# Logic_Level_Output.net
KiCad netlist of a schematic drawn in Altium Designer
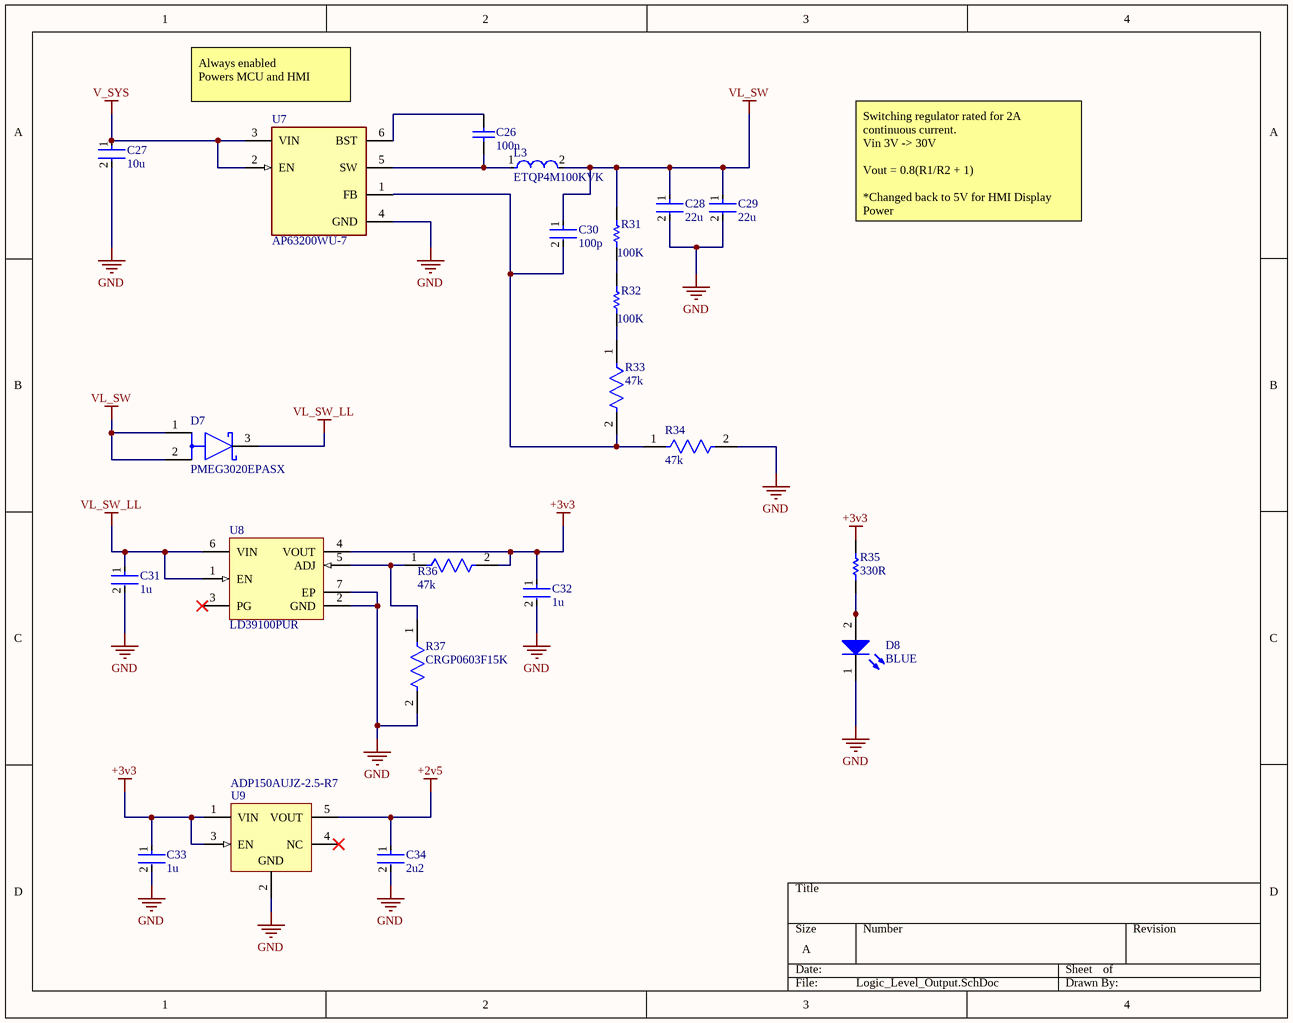
[diagram p0: Logic_Level_Output.SchDoc]

(export (version "E")
  (design (tool "Eeschema 10.0.6"))
  (components
    (comp (ref "C26")
      (value "100n")
      (footprint "CAPC1608X90X35NL15T15")
      (fields (field (name "PART NUMBER") "C0603C104K4RAC7013") (field (name "MANUFACTURER") "Kemet"))
      (libsource (lib "Altium Content Vault") (part "CAP"))
    )
    (comp (ref "C27")
      (value "10u")
      (footprint "FP-C0805X106K8RACAUTO-MFG")
      (description "CAP CER 10UF 10V X7R 0805")
      (fields (field (name "TOLERANCE") "10%"))
      (libsource (lib "Altium Content Vault") (part "b4654b650e69147ec39a6b967a45e02"))
    )
    (comp (ref "C28")
      (value "22u")
      (footprint "FP-C0805C226M8PACTU-MFG")
      (description "CAP CER 22UF 10V X5R 0805")
      (fields (field (name "TOLERANCE") "20%") (field (name "VOLTAGE") "10V"))
      (libsource (lib "Altium Content Vault") (part "02cd4be3c70576c341d710602a673aa"))
    )
    (comp (ref "C29")
      (value "22u")
      (footprint "FP-C0805C226M8PACTU-MFG")
      (description "CAP CER 22UF 10V X5R 0805")
      (fields (field (name "TOLERANCE") "20%") (field (name "VOLTAGE") "10V"))
      (libsource (lib "Altium Content Vault") (part "02cd4be3c70576c341d710602a673aa"))
    )
    (comp (ref "C30")
      (value "100p")
      (footprint "FP-C0603C-CF-MFG")
      (description "CAP CER 100PF 10V X7R 0603")
      (fields
        (field (name "MANUFACTURER") "KEMET")
        (field (name "OCTOPART") "https://octopart.com/c0603c101k8rac7867-kemet-83501928")
      )
      (libsource (lib "Altium Content Vault") (part "b4654b650e69147ec39a6b967a45e02"))
    )
    (comp (ref "C31")
      (value "1u")
      (footprint "FP-0603-L_1_6_0_15-W_0_81-IPC_A")
      (description "General Purpose Ceramic Capacitor, 0603, 1uF, 10%, X5R, 15%, 6.3V")
      (fields (field (name "VOLTAGE") "6.3V") (field (name "TOLERANCE") "10%"))
      (libsource (lib "Altium Content Vault") (part "02cd4be3c70576c341d710602a673aa"))
    )
    (comp (ref "C32")
      (value "1u")
      (footprint "FP-0603-L_1_6_0_15-W_0_81-IPC_A")
      (description "General Purpose Ceramic Capacitor, 0603, 1uF, 10%, X5R, 15%, 6.3V")
      (fields (field (name "VOLTAGE") "6.3V") (field (name "TOLERANCE") "10%"))
      (libsource (lib "Altium Content Vault") (part "02cd4be3c70576c341d710602a673aa"))
    )
    (comp (ref "C33")
      (value "1u")
      (footprint "FP-0603-L_1_6_0_15-W_0_81-IPC_A")
      (description "General Purpose Ceramic Capacitor, 0603, 1uF, 10%, X5R, 15%, 6.3V")
      (fields (field (name "VOLTAGE") "6.3V") (field (name "TOLERANCE") "10%"))
      (libsource (lib "Altium Content Vault") (part "02cd4be3c70576c341d710602a673aa"))
    )
    (comp (ref "C34")
      (value "2u2")
      (footprint "FP-CC0603-DC-MFG")
      (description "CAP CER 2.2UF 50V X5R 0603")
      (fields (field (name "TOLERANCE") "10%"))
      (libsource (lib "Altium Content Vault") (part "11868f565c42a9108669ba33697ecf6"))
    )
    (comp (ref "D7")
      (value "PMEG3020EPASX")
      (footprint "FP-SOT1061D-MFG")
      (description "DIODE SCHOTTKY 30V 2A SOT1061")
      (libsource (lib "Altium Content Vault") (part "9a95c42462f3e72e0f746b9f284d98d"))
    )
    (comp (ref "D8")
      (value "BLUE")
      (footprint "WL-SMCW_0603_150060xx75000")
      (description "Led, Blue, 470 Nm, 3.2 V, 30 Ma, 145 Mcd Rohs Compliant: Yes")
      (libsource (lib "Altium Content Vault") (part "LED_Blue_2A-1K"))
    )
    (comp (ref "L3")
      (value "ETQP4M100KVK")
      (footprint "FP-PCC-M0840M-LP-MFG")
      (description "FIXED IND 10UH 5.2A 45.76 MOHM")
      (fields
        (field (name "OCTOPART") "https://octopart.com/etqp4m100kvk-panasonic-71577993")
        (field (name "MANUFACTURER") "Panasonic")
      )
      (libsource (lib "Altium Content Vault") (part "725321dda6339637d4d059423bc1c3c"))
    )
    (comp (ref "R31")
      (value "100K")
      (footprint "RESC0603(1608)_N")
      (description "100K 0.1W 1% 0603 (1608 Metric)  SMD")
      (fields (field (name "POWER") "0.1 W") (field (name "TOLERANCE") "1 %"))
      (libsource (lib "Altium Content Vault") (part "RES"))
    )
    (comp (ref "R32")
      (value "100K")
      (footprint "RESC0603(1608)_N")
      (description "100K 0.1W 1% 0603 (1608 Metric)  SMD")
      (fields (field (name "POWER") "0.1 W") (field (name "TOLERANCE") "1 %"))
      (libsource (lib "Altium Content Vault") (part "RES"))
    )
    (comp (ref "R33")
      (value "47k")
      (footprint "FP-AT0603-MFG")
      (description "Thin Film Chip Resistors Automotive Grade 47kΩ 1% 50ppm/°C 0603")
      (fields (field (name "TOLERANCE") "1%"))
      (libsource (lib "Altium Content Vault") (part "1029c3af85768c4190bb7ad29bc67b5"))
    )
    (comp (ref "R34")
      (value "47k")
      (footprint "FP-AT0603-MFG")
      (description "Thin Film Chip Resistors Automotive Grade 47kΩ 1% 50ppm/°C 0603")
      (fields (field (name "TOLERANCE") "1%"))
      (libsource (lib "Altium Content Vault") (part "1029c3af85768c4190bb7ad29bc67b5"))
    )
    (comp (ref "R35")
      (value "330R")
      (footprint "RESC1608X55X25NL10T15")
      (description "Chip Resistor, 330 Ohm, +/- 1%, 0.1 W, -55 to 155 degC, 0603 (1608 Metric), RoHS, Tape and Reel")
      (fields (field (name "TOLERANCE") "10%"))
      (libsource (lib "Altium Content Vault") (part "RES-2"))
    )
    (comp (ref "R36")
      (value "47k")
      (footprint "FP-AT0603-MFG")
      (description "Thin Film Chip Resistors Automotive Grade 47kΩ 1% 50ppm/°C 0603")
      (fields (field (name "TOLERANCE") "1%"))
      (libsource (lib "Altium Content Vault") (part "1029c3af85768c4190bb7ad29bc67b5"))
    )
    (comp (ref "R37")
      (value "CRGP0603F15K")
      (footprint "FP-CRGP0603-IPC_C")
      (description "CRGP0603 15KΩ 0.25W ±100ppm/°C 1% 50V")
      (fields
        (field (name "MANUFACTURER") "TE")
        (field (name "OCTOPART") "https://octopart.com/crgp0603f15k-te+connectivity-91018729")
      )
      (libsource (lib "Altium Content Vault") (part "1029c3af85768c4190bb7ad29bc67b5"))
    )
    (comp (ref "U7")
      (value "AP63200WU-7")
      (footprint "FP-TSOT26-MFG")
      (description "IC REG BUCK ADJUSTABLE 2A TSOT26")
      (fields
        (field (name "OCTOPART") "https://octopart.com/ap63200wu-7-diodes+inc.-98099548")
        (field (name "MANUFACTURER") "Diodes Inc.")
      )
      (libsource (lib "Altium Content Vault") (part "2ae3aed49e7ee94ca813948749813a1"))
    )
    (comp (ref "U8")
      (value "LD39100PUR")
      (footprint "DFN6D_M")
      (libsource (lib "Altium Content Vault") (part "PM-REG-LD39050-SQ7A"))
    )
    (comp (ref "U9")
      (value "ADP150AUJZ-2.5-R7")
      (footprint "ADI-UJ-5_N")
      (fields (field (name "MANUFACTURER") "Analog Devices"))
      (libsource (lib "Altium Content Vault") (part "ADI-ADP1XX-UJ-5"))
    )
  )
  (nets
    (net (code "1") (name "+2v5") (class "Default")
      (node (ref "C34") (pin "1") (pinfunction "1_1") (pintype "passive"))
      (node (ref "U9") (pin "5") (pinfunction "VOUT_5") (pintype "power_in"))
    )
    (net (code "2") (name "+3v3") (class "Default")
      (node (ref "C32") (pin "1") (pinfunction "1_1") (pintype "passive"))
      (node (ref "C33") (pin "1") (pinfunction "1_1") (pintype "passive"))
      (node (ref "R35") (pin "2") (pinfunction "2_2") (pintype "passive"))
      (node (ref "R36") (pin "2") (pinfunction "2_2") (pintype "passive"))
      (node (ref "U8") (pin "4") (pinfunction "VOUT_4") (pintype "power_in"))
      (node (ref "U9") (pin "1") (pinfunction "VIN_1") (pintype "power_in"))
      (node (ref "U9") (pin "3") (pinfunction "EN_3") (pintype "input"))
    )
    (net (code "3") (name "GND") (class "Default")
      (node (ref "C27") (pin "2") (pinfunction "2_2") (pintype "passive"))
      (node (ref "C28") (pin "2") (pinfunction "2_2") (pintype "passive"))
      (node (ref "C29") (pin "2") (pinfunction "2_2") (pintype "passive"))
      (node (ref "C31") (pin "2") (pinfunction "2_2") (pintype "passive"))
      (node (ref "C32") (pin "2") (pinfunction "2_2") (pintype "passive"))
      (node (ref "C33") (pin "2") (pinfunction "2_2") (pintype "passive"))
      (node (ref "C34") (pin "2") (pinfunction "2_2") (pintype "passive"))
      (node (ref "D8") (pin "1") (pinfunction "K_1") (pintype "passive"))
      (node (ref "R34") (pin "2") (pinfunction "2_2") (pintype "passive"))
      (node (ref "R37") (pin "2") (pinfunction "2_2") (pintype "passive"))
      (node (ref "U7") (pin "4") (pinfunction "GND_4") (pintype "power_in"))
      (node (ref "U8") (pin "2") (pinfunction "GND_2") (pintype "power_in"))
      (node (ref "U8") (pin "7") (pinfunction "EP_7") (pintype "power_in"))
      (node (ref "U9") (pin "2") (pinfunction "GND_2") (pintype "power_in"))
    )
    (net (code "4") (name "Net-(D8-A)") (class "Default")
      (node (ref "D8") (pin "2") (pinfunction "A_2") (pintype "passive"))
      (node (ref "R35") (pin "1") (pinfunction "1_1") (pintype "passive"))
    )
    (net (code "5") (name "Net-(R31-Pad1)") (class "Default")
      (node (ref "R31") (pin "1") (pinfunction "1_1") (pintype "passive"))
      (node (ref "R32") (pin "2") (pinfunction "2_2") (pintype "passive"))
    )
    (net (code "6") (name "Net-(R32-Pad1)") (class "Default")
      (node (ref "R32") (pin "1") (pinfunction "1_1") (pintype "passive"))
      (node (ref "R33") (pin "1") (pinfunction "1_1") (pintype "passive"))
    )
    (net (code "7") (name "Net-(U7-BST)") (class "Default")
      (node (ref "C26") (pin "2") (pinfunction "2_2") (pintype "passive"))
      (node (ref "U7") (pin "6") (pinfunction "BST_6") (pintype "passive"))
    )
    (net (code "8") (name "Net-(U7-FB)") (class "Default")
      (node (ref "C30") (pin "2") (pinfunction "2_2") (pintype "passive"))
      (node (ref "R33") (pin "2") (pinfunction "2_2") (pintype "passive"))
      (node (ref "R34") (pin "1") (pinfunction "1_1") (pintype "passive"))
      (node (ref "U7") (pin "1") (pinfunction "FB_1") (pintype "passive"))
    )
    (net (code "9") (name "Net-(U7-SW)") (class "Default")
      (node (ref "C26") (pin "1") (pinfunction "1_1") (pintype "passive"))
      (node (ref "L3") (pin "1") (pinfunction "1_1") (pintype "passive"))
      (node (ref "U7") (pin "5") (pinfunction "SW_5") (pintype "passive"))
    )
    (net (code "10") (name "Net-(U8-ADJ)") (class "Default")
      (node (ref "R36") (pin "1") (pinfunction "1_1") (pintype "passive"))
      (node (ref "R37") (pin "1") (pinfunction "1_1") (pintype "passive"))
      (node (ref "U8") (pin "5") (pinfunction "ADJ_5") (pintype "input"))
    )
    (net (code "11") (name "VL_SW") (class "Default")
      (node (ref "C28") (pin "1") (pinfunction "1_1") (pintype "passive"))
      (node (ref "C29") (pin "1") (pinfunction "1_1") (pintype "passive"))
      (node (ref "C30") (pin "1") (pinfunction "1_1") (pintype "passive"))
      (node (ref "D7") (pin "1") (pinfunction "A_1") (pintype "passive"))
      (node (ref "D7") (pin "2") (pinfunction "A_2") (pintype "passive"))
      (node (ref "L3") (pin "2") (pinfunction "2_2") (pintype "passive"))
      (node (ref "R31") (pin "2") (pinfunction "2_2") (pintype "passive"))
    )
    (net (code "12") (name "VL_SW_LL") (class "Default")
      (node (ref "C31") (pin "1") (pinfunction "1_1") (pintype "passive"))
      (node (ref "D7") (pin "3") (pinfunction "C_3") (pintype "passive"))
      (node (ref "U8") (pin "1") (pinfunction "EN_1") (pintype "input"))
      (node (ref "U8") (pin "6") (pinfunction "VIN_6") (pintype "power_in"))
    )
    (net (code "13") (name "V_SYS") (class "Default")
      (node (ref "C27") (pin "1") (pinfunction "1_1") (pintype "passive"))
      (node (ref "U7") (pin "2") (pinfunction "EN_2") (pintype "input"))
      (node (ref "U7") (pin "3") (pinfunction "VIN_3") (pintype "power_in"))
    )
    (net (code "14") (name "unconnected-(U8-PG-Pad3)") (class "Default")
      (node (ref "U8") (pin "3") (pinfunction "PG_3") (pintype "open_collector+no_connect"))
    )
    (net (code "15") (name "unconnected-(U9-NC-Pad4)") (class "Default")
      (node (ref "U9") (pin "4") (pinfunction "NC_4") (pintype "passive+no_connect"))
    )
  )
)
